# PowerStage.net
KiCad netlist of a schematic drawn in Altium Designer
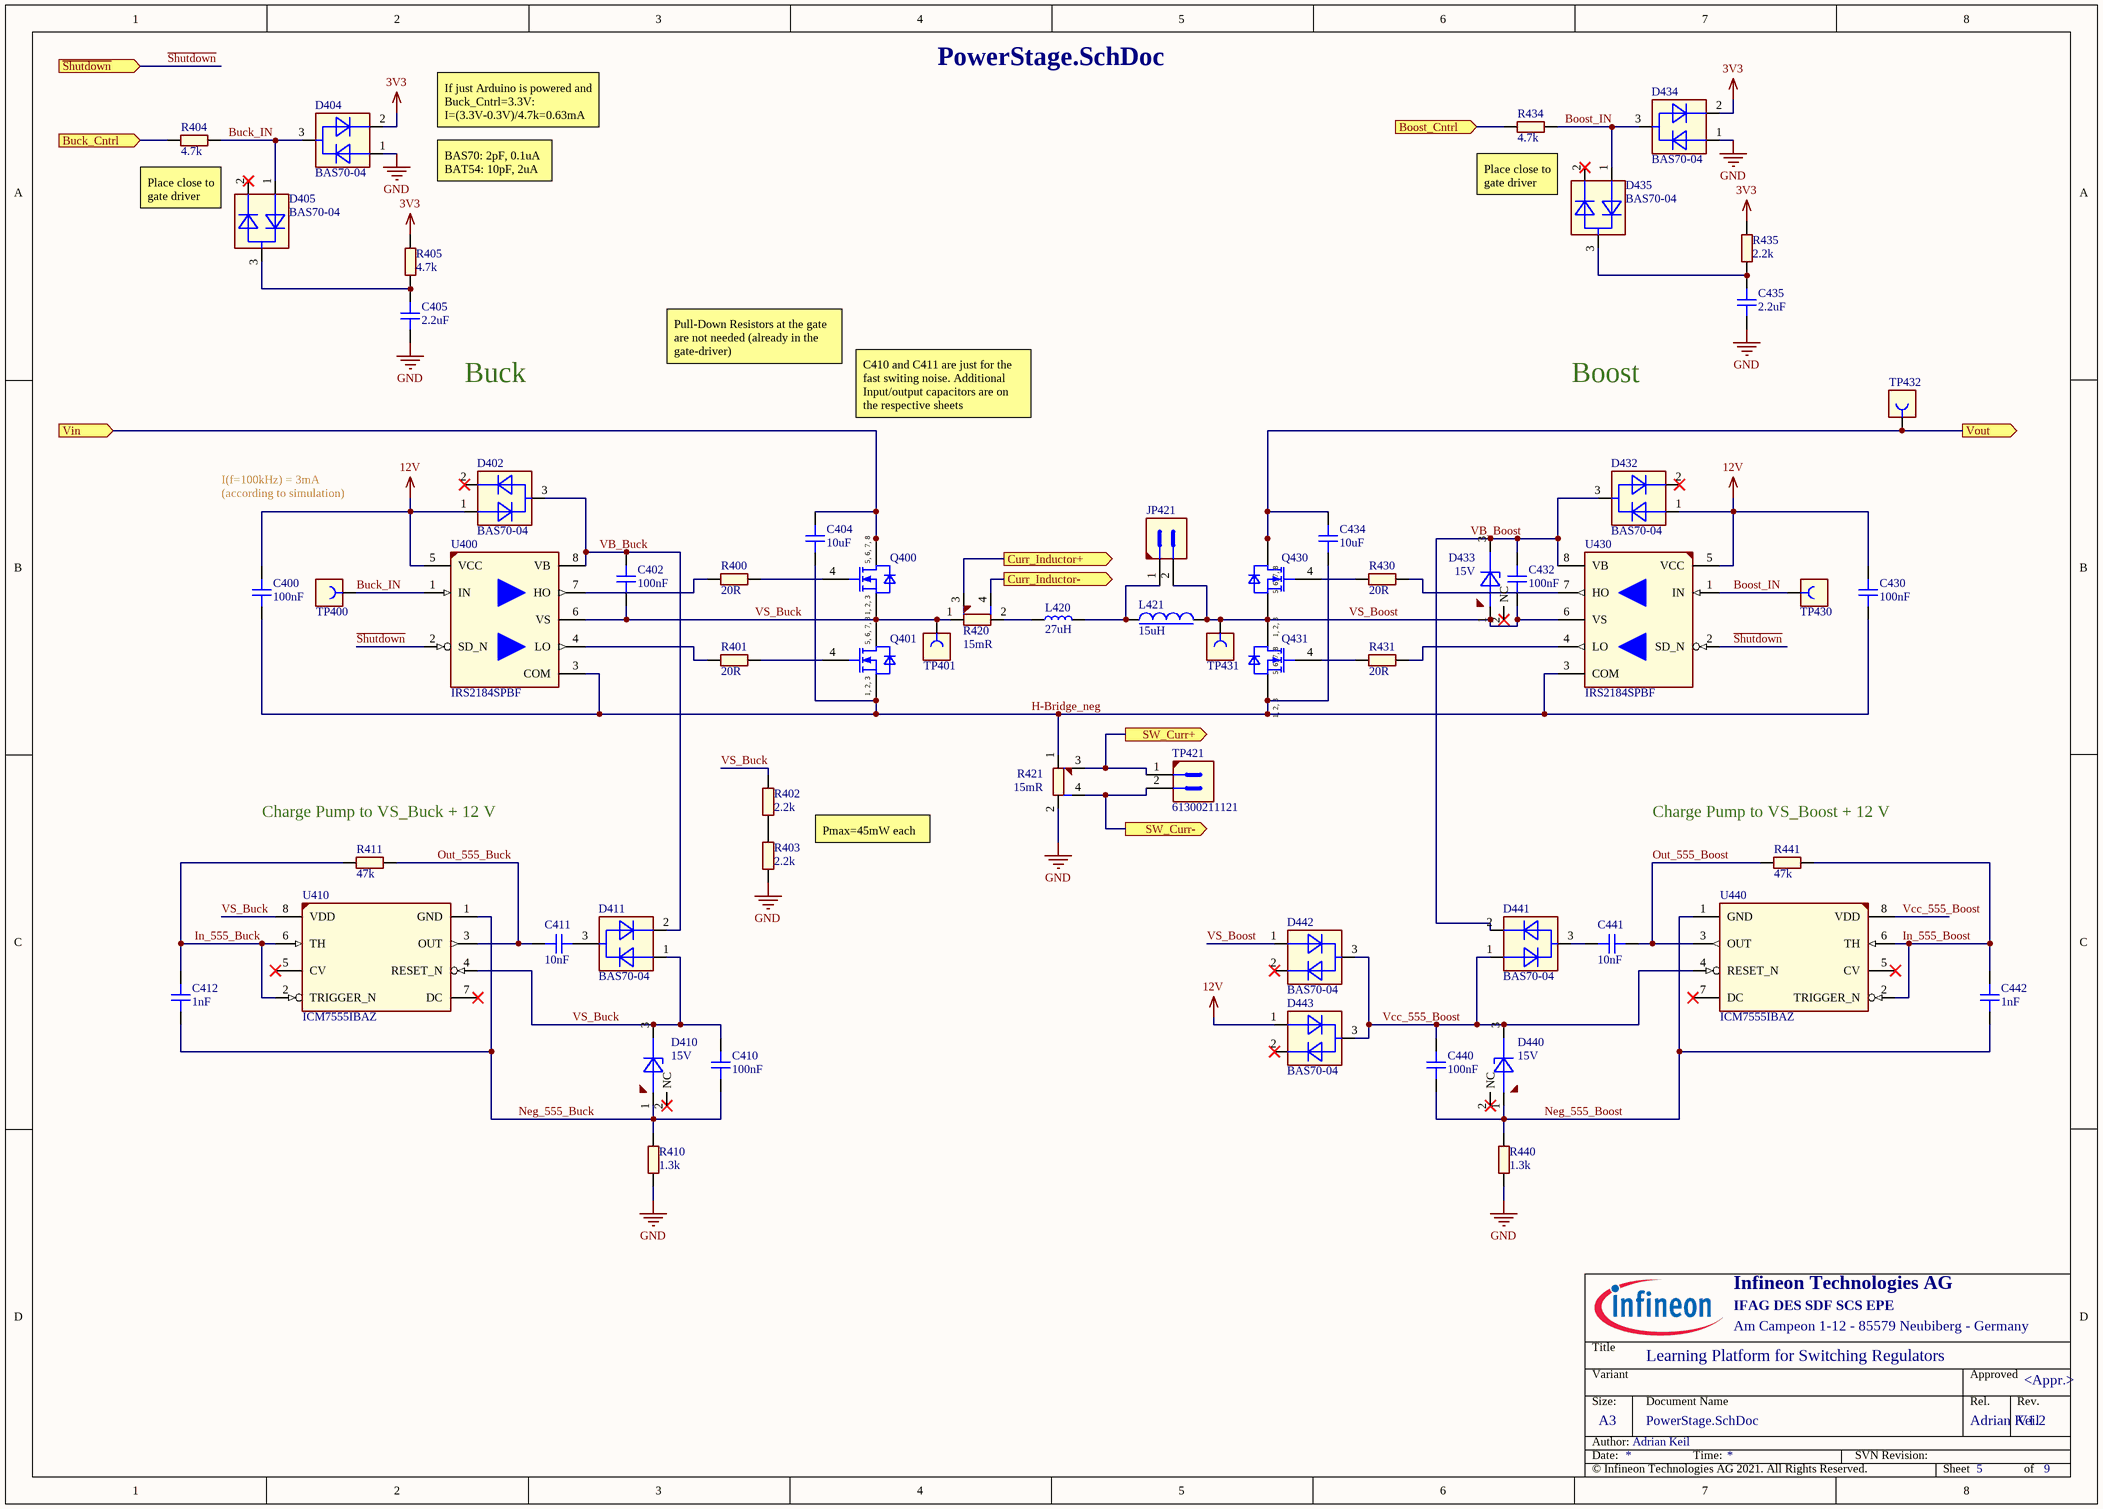
[diagram p0: PowerStage.SchDoc]

(export (version "E")
  (design (tool "Eeschema 10.0.6"))
  (components
    (comp (ref "C400")
      (value "100nF")
      (footprint "CAPC1608X90N-2")
      (description "CAP / CERA / 100nF / 50V / 10% / X7R (EIA) / -55°C to 125°C / 0603 / SMD / -")
      (fields (field (name "MANUFACTURER") "AVX"))
      (libsource (lib "PCBLibraryData") (part "CAP-SGL-STD-02P_00000001"))
    )
    (comp (ref "C402")
      (value "100nF")
      (footprint "CAPC1608X90N-2")
      (description "CAP / CERA / 100nF / 50V / 10% / X7R (EIA) / -55°C to 125°C / 0603 / SMD / -")
      (fields (field (name "MANUFACTURER") "AVX"))
      (libsource (lib "PCBLibraryData") (part "CAP-SGL-STD-02P_00000001"))
    )
    (comp (ref "C404")
      (value "10uF")
      (footprint "CAPC3216X190N-1")
      (description "CAP / CERA / 10uF / 50V / 20% / X5R (EIA) / -55°C to 85°C / 1206 (3216) / SMD / -")
      (fields (field (name "MANUFACTURER") "Taiyo Yuden"))
      (libsource (lib "PCBLibraryData") (part "CAP-SGL-STD-02P_00000001"))
    )
    (comp (ref "C405")
      (value "2.2uF")
      (footprint "CAPC1608X90N-3")
      (description "CAP / CERA / 2.2uF / 25V / 10% / X5R (EIA) / -55°C to 85°C / 0603(1608) / SMD / -")
      (fields (field (name "LEGACY PARTNUMBER") "CAP01010924") (field (name "MANUFACTURER") "MuRata"))
      (libsource (lib "PCBLibraryData") (part "CAP-SGL-STD-02P_00000001"))
    )
    (comp (ref "C410")
      (value "100nF")
      (footprint "CAPC1608X90N-2")
      (description "CAP / CERA / 100nF / 50V / 10% / X7R (EIA) / -55°C to 125°C / 0603 / SMD / -")
      (fields (field (name "MANUFACTURER") "AVX"))
      (libsource (lib "PCBLibraryData") (part "CAP-SGL-STD-02P_00000001"))
    )
    (comp (ref "C411")
      (value "10nF")
      (footprint "CAPC1608X90N-4")
      (description "CAP / CERA / 10nF / 50V / 10% / X8R (EIA) / -55°C to 150°C / 0603(1608) / SMD / -")
      (fields
        (field (name "LEGACY PARTNUMBER") "CAP01010834")
        (field (name "MANUFACTURER") "TDK Corporation")
      )
      (libsource (lib "PCBLibraryData") (part "CAP-SGL-STD-02P_00000001"))
    )
    (comp (ref "C412")
      (value "1nF")
      (footprint "CAPC1608X87N-1")
      (description "CAP / CERA / 1nF / 50V / 10% / X7R (EIA) / -55°C to 125°C / 0603 (1608) / SMD / -")
      (fields (field (name "MANUFACTURER") "Wurth Elektronik"))
      (libsource (lib "PCBLibraryData") (part "CAP-SGL-STD-02P_00000001"))
    )
    (comp (ref "C430")
      (value "100nF")
      (footprint "CAPC1608X90N-2")
      (description "CAP / CERA / 100nF / 50V / 10% / X7R (EIA) / -55°C to 125°C / 0603 / SMD / -")
      (fields (field (name "MANUFACTURER") "AVX"))
      (libsource (lib "PCBLibraryData") (part "CAP-SGL-STD-02P_00000001"))
    )
    (comp (ref "C432")
      (value "100nF")
      (footprint "CAPC1608X90N-2")
      (description "CAP / CERA / 100nF / 50V / 10% / X7R (EIA) / -55°C to 125°C / 0603 / SMD / -")
      (fields (field (name "MANUFACTURER") "AVX"))
      (libsource (lib "PCBLibraryData") (part "CAP-SGL-STD-02P_00000001"))
    )
    (comp (ref "C434")
      (value "10uF")
      (footprint "CAPC3216X190N-1")
      (description "CAP / CERA / 10uF / 50V / 20% / X5R (EIA) / -55°C to 85°C / 1206 (3216) / SMD / -")
      (fields (field (name "MANUFACTURER") "Taiyo Yuden"))
      (libsource (lib "PCBLibraryData") (part "CAP-SGL-STD-02P_00000001"))
    )
    (comp (ref "C435")
      (value "2.2uF")
      (footprint "CAPC1608X90N-3")
      (description "CAP / CERA / 2.2uF / 25V / 10% / X5R (EIA) / -55°C to 85°C / 0603(1608) / SMD / -")
      (fields (field (name "LEGACY PARTNUMBER") "CAP01010924") (field (name "MANUFACTURER") "MuRata"))
      (libsource (lib "PCBLibraryData") (part "CAP-SGL-STD-02P_00000001"))
    )
    (comp (ref "C440")
      (value "100nF")
      (footprint "CAPC1608X90N-2")
      (description "CAP / CERA / 100nF / 50V / 10% / X7R (EIA) / -55°C to 125°C / 0603 / SMD / -")
      (fields (field (name "MANUFACTURER") "AVX"))
      (libsource (lib "PCBLibraryData") (part "CAP-SGL-STD-02P_00000001"))
    )
    (comp (ref "C441")
      (value "10nF")
      (footprint "CAPC1608X90N-4")
      (description "CAP / CERA / 10nF / 50V / 10% / X8R (EIA) / -55°C to 150°C / 0603(1608) / SMD / -")
      (fields
        (field (name "LEGACY PARTNUMBER") "CAP01010834")
        (field (name "MANUFACTURER") "TDK Corporation")
      )
      (libsource (lib "PCBLibraryData") (part "CAP-SGL-STD-02P_00000001"))
    )
    (comp (ref "C442")
      (value "1nF")
      (footprint "CAPC1608X87N-1")
      (description "CAP / CERA / 1nF / 50V / 10% / X7R (EIA) / -55°C to 125°C / 0603 (1608) / SMD / -")
      (fields (field (name "MANUFACTURER") "Wurth Elektronik"))
      (libsource (lib "PCBLibraryData") (part "CAP-SGL-STD-02P_00000001"))
    )
    (comp (ref "D402")
      (value "BAS70-04")
      (footprint "SOT95P240X110-3N-1")
      (description "Silicon Schottky Diode")
      (fields
        (field (name "LEGACY PARTNUMBER") "IFX01400573")
        (field (name "MANUFACTURER") "Infineon Technologies")
      )
      (libsource (lib "") (part "d_dual_a1c2ac3_3p_1"))
    )
    (comp (ref "D404")
      (value "BAS70-04")
      (footprint "SOT95P240X110-3N-1")
      (description "Silicon Schottky Diode")
      (fields
        (field (name "LEGACY PARTNUMBER") "IFX01400573")
        (field (name "MANUFACTURER") "Infineon Technologies")
      )
      (libsource (lib "") (part "d_dual_a1c2ac3_3p_3"))
    )
    (comp (ref "D405")
      (value "BAS70-04")
      (footprint "SOT95P240X110-3N-1")
      (description "Silicon Schottky Diode")
      (fields
        (field (name "LEGACY PARTNUMBER") "IFX01400573")
        (field (name "MANUFACTURER") "Infineon Technologies")
      )
      (libsource (lib "PCBLibraryData") (part "d_dual_a1c2ac3_3p"))
    )
    (comp (ref "D410")
      (value "15V")
      (footprint "SOT95P230X110-3N")
      (description "Voltage regulator diodes")
      (fields (field (name "MANUFACTURER") "Nexperia"))
      (libsource (lib "PCBLibraryData") (part "d_zener_a1c3_3p"))
    )
    (comp (ref "D411")
      (value "BAS70-04")
      (footprint "SOT95P240X110-3N-1")
      (description "Silicon Schottky Diode")
      (fields
        (field (name "LEGACY PARTNUMBER") "IFX01400573")
        (field (name "MANUFACTURER") "Infineon Technologies")
      )
      (libsource (lib "") (part "d_dual_a1c2ac3_3p_3"))
    )
    (comp (ref "D432")
      (value "BAS70-04")
      (footprint "SOT95P240X110-3N-1")
      (description "Silicon Schottky Diode")
      (fields
        (field (name "LEGACY PARTNUMBER") "IFX01400573")
        (field (name "MANUFACTURER") "Infineon Technologies")
      )
      (libsource (lib "") (part "d_dual_a1c2ac3_3p_3"))
    )
    (comp (ref "D433")
      (value "15V")
      (footprint "SOT95P230X110-3N")
      (description "Voltage regulator diodes")
      (fields (field (name "MANUFACTURER") "Nexperia"))
      (libsource (lib "PCBLibraryData") (part "d_zener_a1c3_3p"))
    )
    (comp (ref "D434")
      (value "BAS70-04")
      (footprint "SOT95P240X110-3N-1")
      (description "Silicon Schottky Diode")
      (fields
        (field (name "LEGACY PARTNUMBER") "IFX01400573")
        (field (name "MANUFACTURER") "Infineon Technologies")
      )
      (libsource (lib "") (part "d_dual_a1c2ac3_3p_3"))
    )
    (comp (ref "D435")
      (value "BAS70-04")
      (footprint "SOT95P240X110-3N-1")
      (description "Silicon Schottky Diode")
      (fields
        (field (name "LEGACY PARTNUMBER") "IFX01400573")
        (field (name "MANUFACTURER") "Infineon Technologies")
      )
      (libsource (lib "PCBLibraryData") (part "d_dual_a1c2ac3_3p"))
    )
    (comp (ref "D440")
      (value "15V")
      (footprint "SOT95P230X110-3N")
      (description "Voltage regulator diodes")
      (fields (field (name "MANUFACTURER") "Nexperia"))
      (libsource (lib "PCBLibraryData") (part "d_zener_a1c3_3p"))
    )
    (comp (ref "D441")
      (value "BAS70-04")
      (footprint "SOT95P240X110-3N-1")
      (description "Silicon Schottky Diode")
      (fields
        (field (name "LEGACY PARTNUMBER") "IFX01400573")
        (field (name "MANUFACTURER") "Infineon Technologies")
      )
      (libsource (lib "") (part "d_dual_a1c2ac3_3p_1"))
    )
    (comp (ref "D442")
      (value "BAS70-04")
      (footprint "SOT95P240X110-3N-1")
      (description "Silicon Schottky Diode")
      (fields
        (field (name "LEGACY PARTNUMBER") "IFX01400573")
        (field (name "MANUFACTURER") "Infineon Technologies")
      )
      (libsource (lib "") (part "d_dual_a1c2ac3_3p_2"))
    )
    (comp (ref "D443")
      (value "BAS70-04")
      (footprint "SOT95P240X110-3N-1")
      (description "Silicon Schottky Diode")
      (fields
        (field (name "LEGACY PARTNUMBER") "IFX01400573")
        (field (name "MANUFACTURER") "Infineon Technologies")
      )
      (libsource (lib "") (part "d_dual_a1c2ac3_3p_2"))
    )
    (comp (ref "JP421")
      (value "61300211121")
      (footprint "CON-M-THT-61300211121")
      (description "Header, 2.54mm Pitch, 2 pin, Vertical, Single Row")
      (fields
        (field (name "LEGACY PARTNUMBER") "CON01500943")
        (field (name "MANUFACTURER") "Wurth Elektronik")
      )
      (libsource (lib "") (part "Header 2_1"))
    )
    (comp (ref "L420")
      (value "27uH")
      (footprint "INDM120120X1000N")
      (fields (field (name "MANUFACTURER") "Wurth Elektronik"))
      (libsource (lib "PCBLibraryData") (part "IND-SGL-STD-02P_00000015"))
    )
    (comp (ref "L421")
      (value "15uH")
      (footprint "IND-SMD-SRP6060FA")
      (fields (field (name "MANUFACTURER") "Bourns"))
      (libsource (lib "PCBLibraryData") (part "IND-SGL-STD-COR-02P_00000016"))
    )
    (comp (ref "Q400")
      (value "igfet_n_ch_enh_dio_1s2s3s4g5d6d7d8d_8p")
      (footprint "INF-PG-TSDSON-8-FL")
      (description "OptiMOS Power - MOSFET, 60 V")
      (fields
        (field (name "LEGACY PARTNUMBER") "IFX01400359")
        (field (name "MANUFACTURER") "Infineon Technologies")
      )
      (libsource (lib "PCBLibraryData") (part "igfet_n_ch_enh_dio_1s2s3s4g5d6d7d8d_8p"))
    )
    (comp (ref "Q401")
      (value "igfet_n_ch_enh_dio_1s2s3s4g5d6d7d8d_8p")
      (footprint "INF-PG-TSDSON-8-FL")
      (description "OptiMOS Power - MOSFET, 60 V")
      (fields
        (field (name "LEGACY PARTNUMBER") "IFX01400359")
        (field (name "MANUFACTURER") "Infineon Technologies")
      )
      (libsource (lib "PCBLibraryData") (part "igfet_n_ch_enh_dio_1s2s3s4g5d6d7d8d_8p"))
    )
    (comp (ref "Q430")
      (value "igfet_n_ch_enh_dio_1s2s3s4g5d6d7d8d_8p")
      (footprint "INF-PG-TSDSON-8-FL")
      (description "OptiMOS Power - MOSFET, 60 V")
      (fields
        (field (name "LEGACY PARTNUMBER") "IFX01400359")
        (field (name "MANUFACTURER") "Infineon Technologies")
      )
      (libsource (lib "PCBLibraryData") (part "igfet_n_ch_enh_dio_1s2s3s4g5d6d7d8d_8p"))
    )
    (comp (ref "Q431")
      (value "igfet_n_ch_enh_dio_1s2s3s4g5d6d7d8d_8p")
      (footprint "INF-PG-TSDSON-8-FL")
      (description "OptiMOS Power - MOSFET, 60 V")
      (fields
        (field (name "LEGACY PARTNUMBER") "IFX01400359")
        (field (name "MANUFACTURER") "Infineon Technologies")
      )
      (libsource (lib "PCBLibraryData") (part "igfet_n_ch_enh_dio_1s2s3s4g5d6d7d8d_8p"))
    )
    (comp (ref "R400")
      (value "20R")
      (footprint "RESC1609X50N")
      (description "RES / STD / 20R / 100mW / 1% / 100ppm/K / -55°C to 155°C / 0603 / SMD / -")
      (fields (field (name "LEGACY PARTNUMBER") "RES01800947") (field (name "MANUFACTURER") "Vishay"))
      (libsource (lib "PCBLibraryData") (part "RES-SGL-STD-02P_00000006"))
    )
    (comp (ref "R401")
      (value "20R")
      (footprint "RESC1609X50N")
      (description "RES / STD / 20R / 100mW / 1% / 100ppm/K / -55°C to 155°C / 0603 / SMD / -")
      (fields (field (name "LEGACY PARTNUMBER") "RES01800947") (field (name "MANUFACTURER") "Vishay"))
      (libsource (lib "PCBLibraryData") (part "RES-SGL-STD-02P_00000006"))
    )
    (comp (ref "R402")
      (value "2.2k")
      (footprint "RESC1609X50N")
      (description "RES / STD / 2.2k / 100mW / 1% / 100ppm/K / -55°C to 155°C / 0603 / SMD / -")
      (fields (field (name "LEGACY PARTNUMBER") "RES01801179") (field (name "MANUFACTURER") "Vishay"))
      (libsource (lib "") (part "RES-SGL-STD-02P_00000006_1"))
    )
    (comp (ref "R403")
      (value "2.2k")
      (footprint "RESC1609X50N")
      (description "RES / STD / 2.2k / 100mW / 1% / 100ppm/K / -55°C to 155°C / 0603 / SMD / -")
      (fields (field (name "LEGACY PARTNUMBER") "RES01801179") (field (name "MANUFACTURER") "Vishay"))
      (libsource (lib "") (part "RES-SGL-STD-02P_00000006_1"))
    )
    (comp (ref "R404")
      (value "4.7k")
      (footprint "RESC1609X50N")
      (description "RES / STD / 4.7k / 100mW / 1% / 100ppm/K / -55°C to 155°C / 0603 / SMD / -")
      (fields (field (name "LEGACY PARTNUMBER") "RES01801219") (field (name "MANUFACTURER") "Vishay"))
      (libsource (lib "") (part "RES-SGL-STD-02P_00000006_3"))
    )
    (comp (ref "R405")
      (value "4.7k")
      (footprint "RESC1609X50N")
      (description "RES / STD / 4.7k / 100mW / 1% / 100ppm/K / -55°C to 155°C / 0603 / SMD / -")
      (fields (field (name "LEGACY PARTNUMBER") "RES01801219") (field (name "MANUFACTURER") "Vishay"))
      (libsource (lib "") (part "RES-SGL-STD-02P_00000006_2"))
    )
    (comp (ref "R410")
      (value "1.3k")
      (footprint "RESC1609X50N")
      (description "RES / STD / 1.3k / 100mW / 1% / 100ppm/K / -55°C to 155°C / 0603 / SMD / -")
      (fields (field (name "LEGACY PARTNUMBER") "RES01801155") (field (name "MANUFACTURER") "Vishay"))
      (libsource (lib "") (part "RES-SGL-STD-02P_00000006_2"))
    )
    (comp (ref "R411")
      (value "47k")
      (footprint "RESC1609X50N")
      (description "RES / STD / 47k / 100mW / 1% / 100ppm/K / -55°C to 155°C / 0603 / SMD / -")
      (fields (field (name "LEGACY PARTNUMBER") "RES01801333") (field (name "MANUFACTURER") "Vishay"))
      (libsource (lib "PCBLibraryData") (part "RES-SGL-STD-02P_00000006"))
    )
    (comp (ref "R420")
      (value "15mR")
      (footprint "RES-SMD-L4T12")
      (description "RES / STD / 15mR / 500mW / 1% / 75ppm/K / -55°C to 155°C / 1206 (3216) / SMD / -")
      (fields (field (name "MANUFACTURER") "Ohmite"))
      (libsource (lib "") (part "RES-SHT-STD-04P_00097BE5_1"))
    )
    (comp (ref "R421")
      (value "15mR")
      (footprint "RES-SMD-L4T12")
      (description "RES / STD / 15mR / 500mW / 1% / 75ppm/K / -55°C to 155°C / 1206 (3216) / SMD / -")
      (fields (field (name "MANUFACTURER") "Ohmite"))
      (libsource (lib "PCBLibraryData") (part "RES-SHT-STD-04P_00097BE5"))
    )
    (comp (ref "R430")
      (value "20R")
      (footprint "RESC1609X50N")
      (description "RES / STD / 20R / 100mW / 1% / 100ppm/K / -55°C to 155°C / 0603 / SMD / -")
      (fields (field (name "LEGACY PARTNUMBER") "RES01800947") (field (name "MANUFACTURER") "Vishay"))
      (libsource (lib "PCBLibraryData") (part "RES-SGL-STD-02P_00000006"))
    )
    (comp (ref "R431")
      (value "20R")
      (footprint "RESC1609X50N")
      (description "RES / STD / 20R / 100mW / 1% / 100ppm/K / -55°C to 155°C / 0603 / SMD / -")
      (fields (field (name "LEGACY PARTNUMBER") "RES01800947") (field (name "MANUFACTURER") "Vishay"))
      (libsource (lib "PCBLibraryData") (part "RES-SGL-STD-02P_00000006"))
    )
    (comp (ref "R434")
      (value "4.7k")
      (footprint "RESC1609X50N")
      (description "RES / STD / 4.7k / 100mW / 1% / 100ppm/K / -55°C to 155°C / 0603 / SMD / -")
      (fields (field (name "LEGACY PARTNUMBER") "RES01801219") (field (name "MANUFACTURER") "Vishay"))
      (libsource (lib "") (part "RES-SGL-STD-02P_00000006_3"))
    )
    (comp (ref "R435")
      (value "2.2k")
      (footprint "RESC1609X50N")
      (description "RES / STD / 2.2k / 100mW / 1% / 100ppm/K / -55°C to 155°C / 0603 / SMD / -")
      (fields (field (name "LEGACY PARTNUMBER") "RES01801179") (field (name "MANUFACTURER") "Vishay"))
      (libsource (lib "") (part "RES-SGL-STD-02P_00000006_1"))
    )
    (comp (ref "R440")
      (value "1.3k")
      (footprint "RESC1609X50N")
      (description "RES / STD / 1.3k / 100mW / 1% / 100ppm/K / -55°C to 155°C / 0603 / SMD / -")
      (fields (field (name "LEGACY PARTNUMBER") "RES01801155") (field (name "MANUFACTURER") "Vishay"))
      (libsource (lib "") (part "RES-SGL-STD-02P_00000006_2"))
    )
    (comp (ref "R441")
      (value "47k")
      (footprint "RESC1609X50N")
      (description "RES / STD / 47k / 100mW / 1% / 100ppm/K / -55°C to 155°C / 0603 / SMD / -")
      (fields (field (name "LEGACY PARTNUMBER") "RES01801333") (field (name "MANUFACTURER") "Vishay"))
      (libsource (lib "") (part "RES-SGL-STD-02P_00000006_2"))
    )
    (comp (ref "TP400")
      (value "S1751-46R")
      (footprint "CON-SMD-TT-S1751-46")
      (description "Test Terminal, Surface Mount (Tape and Reeled Components)")
      (fields (field (name "LEGACY PARTNUMBER") "CON01501015") (field (name "MANUFACTURER") "Harwin"))
      (libsource (lib "") (part "connector_1_f_2"))
    )
    (comp (ref "TP401")
      (value "S1751-46R")
      (footprint "CON-SMD-TT-S1751-46")
      (description "Test Terminal, Surface Mount (Tape and Reeled Components)")
      (fields (field (name "LEGACY PARTNUMBER") "CON01501015") (field (name "MANUFACTURER") "Harwin"))
      (libsource (lib "PCBLibraryData") (part "connector_1_f"))
    )
    (comp (ref "TP421")
      (value "61300211121")
      (footprint "CON-M-THT-61300211121")
      (description "Header, 2.54mm Pitch, 2 pin, Vertical, Single Row")
      (fields
        (field (name "LEGACY PARTNUMBER") "CON01500943")
        (field (name "MANUFACTURER") "Wurth Elektronik")
      )
      (libsource (lib "PCBLibraryData") (part "Header 2"))
    )
    (comp (ref "TP430")
      (value "S1751-46R")
      (footprint "CON-SMD-TT-S1751-46")
      (description "Test Terminal, Surface Mount (Tape and Reeled Components)")
      (fields (field (name "LEGACY PARTNUMBER") "CON01501015") (field (name "MANUFACTURER") "Harwin"))
      (libsource (lib "") (part "connector_1_f_3"))
    )
    (comp (ref "TP431")
      (value "S1751-46R")
      (footprint "CON-SMD-TT-S1751-46")
      (description "Test Terminal, Surface Mount (Tape and Reeled Components)")
      (fields (field (name "LEGACY PARTNUMBER") "CON01501015") (field (name "MANUFACTURER") "Harwin"))
      (libsource (lib "PCBLibraryData") (part "connector_1_f"))
    )
    (comp (ref "TP432")
      (value "S1751-46R")
      (footprint "CON-SMD-TT-S1751-46")
      (description "Test Terminal, Surface Mount (Tape and Reeled Components)")
      (fields (field (name "LEGACY PARTNUMBER") "CON01501015") (field (name "MANUFACTURER") "Harwin"))
      (libsource (lib "") (part "connector_1_f_1"))
    )
    (comp (ref "U400")
      (value "IRS2184SPBF")
      (footprint "SOIC127P600X175-8N-12-V")
      (fields (field (name "MANUFACTURER") "Infineon Technologies"))
      (libsource (lib "PCBLibraryData") (part "IRS2184S"))
    )
    (comp (ref "U410")
      (value "ICM7555IBAZ")
      (footprint "SOIC127P600X175-8N-12")
      (description "General Purpose Timers")
      (fields (field (name "MANUFACTURER") "Renesas"))
      (libsource (lib "") (part "ICM7555_1"))
    )
    (comp (ref "U430")
      (value "IRS2184SPBF")
      (footprint "SOIC127P600X175-8N-12-V")
      (fields (field (name "MANUFACTURER") "Infineon Technologies"))
      (libsource (lib "") (part "IRS2184S_1"))
    )
    (comp (ref "U440")
      (value "ICM7555IBAZ")
      (footprint "SOIC127P600X175-8N-12")
      (description "General Purpose Timers")
      (fields (field (name "MANUFACTURER") "Renesas"))
      (libsource (lib "PCBLibraryData") (part "ICM7555"))
    )
  )
  (nets
    (net (code "1") (name "/Boost_Cntrl") (class "Default")
      (node (ref "R434") (pin "1") (pinfunction "1_1") (pintype "passive"))
    )
    (net (code "2") (name "/Boost_IN") (class "Default")
      (node (ref "D434") (pin "3") (pinfunction "ANODE_/_CATHODE_3") (pintype "passive"))
      (node (ref "D435") (pin "1") (pinfunction "ANODE_1") (pintype "passive"))
      (node (ref "R434") (pin "2") (pinfunction "2_2") (pintype "passive"))
      (node (ref "TP430") (pin "1") (pinfunction "1_1") (pintype "passive"))
      (node (ref "U430") (pin "1") (pinfunction "IN_1") (pintype "input"))
    )
    (net (code "3") (name "/Buck_Cntrl") (class "Default")
      (node (ref "R404") (pin "1") (pinfunction "1_1") (pintype "passive"))
    )
    (net (code "4") (name "/Buck_IN") (class "Default")
      (node (ref "D404") (pin "3") (pinfunction "ANODE_/_CATHODE_3") (pintype "passive"))
      (node (ref "D405") (pin "1") (pinfunction "ANODE_1") (pintype "passive"))
      (node (ref "R404") (pin "2") (pinfunction "2_2") (pintype "passive"))
      (node (ref "TP400") (pin "1") (pinfunction "1_1") (pintype "passive"))
      (node (ref "U400") (pin "1") (pinfunction "IN_1") (pintype "input"))
    )
    (net (code "5") (name "/Curr_Inductor+") (class "Default")
      (node (ref "R420") (pin "3") (pinfunction "I1_3") (pintype "passive"))
    )
    (net (code "6") (name "/Curr_Inductor-") (class "Default")
      (node (ref "R420") (pin "4") (pinfunction "I2_4") (pintype "passive"))
    )
    (net (code "7") (name "/H-Bridge_neg") (class "Default")
      (node (ref "C400") (pin "1") (pinfunction "1_1") (pintype "passive"))
      (node (ref "C404") (pin "1") (pinfunction "1_1") (pintype "passive"))
      (node (ref "C430") (pin "1") (pinfunction "1_1") (pintype "passive"))
      (node (ref "C434") (pin "1") (pinfunction "1_1") (pintype "passive"))
      (node (ref "Q401") (pin "1") (pinfunction "SOURCE_1") (pintype "passive"))
      (node (ref "Q401") (pin "2") (pinfunction "SOURCE_2") (pintype "passive"))
      (node (ref "Q401") (pin "3") (pinfunction "SOURCE_3") (pintype "passive"))
      (node (ref "Q431") (pin "1") (pinfunction "SOURCE_1") (pintype "passive"))
      (node (ref "Q431") (pin "2") (pinfunction "SOURCE_2") (pintype "passive"))
      (node (ref "Q431") (pin "3") (pinfunction "SOURCE_3") (pintype "passive"))
      (node (ref "R421") (pin "1") (pinfunction "V1_1") (pintype "passive"))
      (node (ref "U400") (pin "3") (pinfunction "COM_3") (pintype "passive"))
      (node (ref "U430") (pin "3") (pinfunction "COM_3") (pintype "passive"))
    )
    (net (code "8") (name "/In_555_Boost") (class "Default")
      (node (ref "C442") (pin "2") (pinfunction "2_2") (pintype "passive"))
      (node (ref "R441") (pin "2") (pinfunction "2_2") (pintype "passive"))
      (node (ref "U440") (pin "2") (pinfunction "TRIGGER_N_2") (pintype "input"))
      (node (ref "U440") (pin "6") (pinfunction "TH_6") (pintype "input"))
    )
    (net (code "9") (name "/In_555_Buck") (class "Default")
      (node (ref "C412") (pin "2") (pinfunction "2_2") (pintype "passive"))
      (node (ref "R411") (pin "2") (pinfunction "2_2") (pintype "passive"))
      (node (ref "U410") (pin "2") (pinfunction "TRIGGER_N_2") (pintype "input"))
      (node (ref "U410") (pin "6") (pinfunction "TH_6") (pintype "input"))
    )
    (net (code "10") (name "/Neg_555_Boost") (class "Default")
      (node (ref "C440") (pin "1") (pinfunction "1_1") (pintype "passive"))
      (node (ref "C442") (pin "1") (pinfunction "1_1") (pintype "passive"))
      (node (ref "D440") (pin "1") (pinfunction "ANODE_1") (pintype "passive"))
      (node (ref "R440") (pin "2") (pinfunction "2_2") (pintype "passive"))
      (node (ref "U440") (pin "1") (pinfunction "GND_1") (pintype "power_in"))
    )
    (net (code "11") (name "/Neg_555_Buck") (class "Default")
      (node (ref "C410") (pin "1") (pinfunction "1_1") (pintype "passive"))
      (node (ref "C412") (pin "1") (pinfunction "1_1") (pintype "passive"))
      (node (ref "D410") (pin "1") (pinfunction "ANODE_1") (pintype "passive"))
      (node (ref "R410") (pin "2") (pinfunction "2_2") (pintype "passive"))
      (node (ref "U410") (pin "1") (pinfunction "GND_1") (pintype "power_in"))
    )
    (net (code "12") (name "/Out_555_Boost") (class "Default")
      (node (ref "C441") (pin "1") (pinfunction "1_1") (pintype "passive"))
      (node (ref "R441") (pin "1") (pinfunction "1_1") (pintype "passive"))
      (node (ref "U440") (pin "3") (pinfunction "OUT_3") (pintype "output"))
    )
    (net (code "13") (name "/Out_555_Buck") (class "Default")
      (node (ref "C411") (pin "2") (pinfunction "2_2") (pintype "passive"))
      (node (ref "R411") (pin "1") (pinfunction "1_1") (pintype "passive"))
      (node (ref "U410") (pin "3") (pinfunction "OUT_3") (pintype "output"))
    )
    (net (code "14") (name "/SW_Curr+") (class "Default")
      (node (ref "R421") (pin "3") (pinfunction "I1_3") (pintype "passive"))
      (node (ref "TP421") (pin "1") (pinfunction "1_1") (pintype "passive"))
    )
    (net (code "15") (name "/SW_Curr-") (class "Default")
      (node (ref "R421") (pin "4") (pinfunction "I2_4") (pintype "passive"))
      (node (ref "TP421") (pin "2") (pinfunction "2_2") (pintype "passive"))
    )
    (net (code "16") (name "/Shutdown") (class "Default")
      (node (ref "U400") (pin "2") (pinfunction "SD_N_2") (pintype "input"))
      (node (ref "U430") (pin "2") (pinfunction "SD_N_2") (pintype "input"))
    )
    (net (code "17") (name "/VB_Boost") (class "Default")
      (node (ref "C432") (pin "2") (pinfunction "2_2") (pintype "passive"))
      (node (ref "D432") (pin "3") (pinfunction "ANODE_/_CATHODE_3") (pintype "passive"))
      (node (ref "D433") (pin "3") (pinfunction "CATHODE_3") (pintype "passive"))
      (node (ref "D441") (pin "2") (pinfunction "CATHODE_2") (pintype "passive"))
      (node (ref "U430") (pin "8") (pinfunction "VB_8") (pintype "power_in"))
    )
    (net (code "18") (name "/VB_Buck") (class "Default")
      (node (ref "C402") (pin "2") (pinfunction "2_2") (pintype "passive"))
      (node (ref "D402") (pin "3") (pinfunction "ANODE_/_CATHODE_3") (pintype "passive"))
      (node (ref "D411") (pin "2") (pinfunction "CATHODE_2") (pintype "passive"))
      (node (ref "U400") (pin "8") (pinfunction "VB_8") (pintype "power_in"))
    )
    (net (code "19") (name "/VS_Boost") (class "Default")
      (node (ref "C432") (pin "1") (pinfunction "1_1") (pintype "passive"))
      (node (ref "D433") (pin "1") (pinfunction "ANODE_1") (pintype "passive"))
      (node (ref "D442") (pin "1") (pinfunction "ANODE_1") (pintype "passive"))
      (node (ref "JP421") (pin "2") (pinfunction "2_2") (pintype "passive"))
      (node (ref "L421") (pin "2") (pinfunction "2_2") (pintype "passive"))
      (node (ref "Q430") (pin "1") (pinfunction "SOURCE_1") (pintype "passive"))
      (node (ref "Q430") (pin "2") (pinfunction "SOURCE_2") (pintype "passive"))
      (node (ref "Q430") (pin "3") (pinfunction "SOURCE_3") (pintype "passive"))
      (node (ref "Q431") (pin "5") (pinfunction "DRAIN_5") (pintype "passive"))
      (node (ref "Q431") (pin "6") (pinfunction "DRAIN_6") (pintype "passive"))
      (node (ref "Q431") (pin "7") (pinfunction "DRAIN_7") (pintype "passive"))
      (node (ref "Q431") (pin "8") (pinfunction "DRAIN_8") (pintype "passive"))
      (node (ref "TP431") (pin "1") (pinfunction "1_1") (pintype "passive"))
      (node (ref "U430") (pin "6") (pinfunction "VS_6") (pintype "power_in"))
    )
    (net (code "20") (name "/VS_Buck") (class "Default")
      (node (ref "C402") (pin "1") (pinfunction "1_1") (pintype "passive"))
      (node (ref "C410") (pin "2") (pinfunction "2_2") (pintype "passive"))
      (node (ref "D410") (pin "3") (pinfunction "CATHODE_3") (pintype "passive"))
      (node (ref "D411") (pin "1") (pinfunction "ANODE_1") (pintype "passive"))
      (node (ref "Q400") (pin "1") (pinfunction "SOURCE_1") (pintype "passive"))
      (node (ref "Q400") (pin "2") (pinfunction "SOURCE_2") (pintype "passive"))
      (node (ref "Q400") (pin "3") (pinfunction "SOURCE_3") (pintype "passive"))
      (node (ref "Q401") (pin "5") (pinfunction "DRAIN_5") (pintype "passive"))
      (node (ref "Q401") (pin "6") (pinfunction "DRAIN_6") (pintype "passive"))
      (node (ref "Q401") (pin "7") (pinfunction "DRAIN_7") (pintype "passive"))
      (node (ref "Q401") (pin "8") (pinfunction "DRAIN_8") (pintype "passive"))
      (node (ref "R402") (pin "1") (pinfunction "1_1") (pintype "passive"))
      (node (ref "R420") (pin "1") (pinfunction "V1_1") (pintype "passive"))
      (node (ref "TP401") (pin "1") (pinfunction "1_1") (pintype "passive"))
      (node (ref "U400") (pin "6") (pinfunction "VS_6") (pintype "power_in"))
      (node (ref "U410") (pin "4") (pinfunction "RESET_N_4") (pintype "input"))
      (node (ref "U410") (pin "8") (pinfunction "VDD_8") (pintype "power_in"))
    )
    (net (code "21") (name "/Vcc_555_Boost") (class "Default")
      (node (ref "C440") (pin "2") (pinfunction "2_2") (pintype "passive"))
      (node (ref "D440") (pin "3") (pinfunction "CATHODE_3") (pintype "passive"))
      (node (ref "D441") (pin "1") (pinfunction "ANODE_1") (pintype "passive"))
      (node (ref "D442") (pin "3") (pinfunction "ANODE_/_CATHODE_3") (pintype "passive"))
      (node (ref "D443") (pin "3") (pinfunction "ANODE_/_CATHODE_3") (pintype "passive"))
      (node (ref "U440") (pin "4") (pinfunction "RESET_N_4") (pintype "input"))
      (node (ref "U440") (pin "8") (pinfunction "VDD_8") (pintype "power_in"))
    )
    (net (code "22") (name "/Vin") (class "Default")
      (node (ref "C404") (pin "2") (pinfunction "2_2") (pintype "passive"))
      (node (ref "Q400") (pin "5") (pinfunction "DRAIN_5") (pintype "passive"))
      (node (ref "Q400") (pin "6") (pinfunction "DRAIN_6") (pintype "passive"))
      (node (ref "Q400") (pin "7") (pinfunction "DRAIN_7") (pintype "passive"))
      (node (ref "Q400") (pin "8") (pinfunction "DRAIN_8") (pintype "passive"))
    )
    (net (code "23") (name "/Vout") (class "Default")
      (node (ref "C434") (pin "2") (pinfunction "2_2") (pintype "passive"))
      (node (ref "Q430") (pin "5") (pinfunction "DRAIN_5") (pintype "passive"))
      (node (ref "Q430") (pin "6") (pinfunction "DRAIN_6") (pintype "passive"))
      (node (ref "Q430") (pin "7") (pinfunction "DRAIN_7") (pintype "passive"))
      (node (ref "Q430") (pin "8") (pinfunction "DRAIN_8") (pintype "passive"))
      (node (ref "TP432") (pin "1") (pinfunction "1_1") (pintype "passive"))
    )
    (net (code "24") (name "3V3") (class "Default")
      (node (ref "D404") (pin "2") (pinfunction "CATHODE_2") (pintype "passive"))
      (node (ref "D434") (pin "2") (pinfunction "CATHODE_2") (pintype "passive"))
      (node (ref "R405") (pin "2") (pinfunction "2_2") (pintype "passive"))
      (node (ref "R435") (pin "1") (pinfunction "1_1") (pintype "passive"))
    )
    (net (code "25") (name "12V") (class "Default")
      (node (ref "C400") (pin "2") (pinfunction "2_2") (pintype "passive"))
      (node (ref "C430") (pin "2") (pinfunction "2_2") (pintype "passive"))
      (node (ref "D402") (pin "1") (pinfunction "ANODE_1") (pintype "passive"))
      (node (ref "D432") (pin "1") (pinfunction "ANODE_1") (pintype "passive"))
      (node (ref "D443") (pin "1") (pinfunction "ANODE_1") (pintype "passive"))
      (node (ref "U400") (pin "5") (pinfunction "VCC_5") (pintype "power_in"))
      (node (ref "U430") (pin "5") (pinfunction "VCC_5") (pintype "power_in"))
    )
    (net (code "26") (name "GND") (class "Default")
      (node (ref "C405") (pin "1") (pinfunction "1_1") (pintype "passive"))
      (node (ref "C435") (pin "1") (pinfunction "1_1") (pintype "passive"))
      (node (ref "D404") (pin "1") (pinfunction "ANODE_1") (pintype "passive"))
      (node (ref "D434") (pin "1") (pinfunction "ANODE_1") (pintype "passive"))
      (node (ref "R403") (pin "2") (pinfunction "2_2") (pintype "passive"))
      (node (ref "R410") (pin "1") (pinfunction "1_1") (pintype "passive"))
      (node (ref "R421") (pin "2") (pinfunction "V2_2") (pintype "passive"))
      (node (ref "R440") (pin "1") (pinfunction "1_1") (pintype "passive"))
    )
    (net (code "27") (name "Net-(D405-ANODE_{slash}_CATHODE)") (class "Default")
      (node (ref "C405") (pin "2") (pinfunction "2_2") (pintype "passive"))
      (node (ref "D405") (pin "3") (pinfunction "ANODE_/_CATHODE_3") (pintype "passive"))
      (node (ref "R405") (pin "1") (pinfunction "1_1") (pintype "passive"))
    )
    (net (code "28") (name "Net-(D411-ANODE_{slash}_CATHODE)") (class "Default")
      (node (ref "C411") (pin "1") (pinfunction "1_1") (pintype "passive"))
      (node (ref "D411") (pin "3") (pinfunction "ANODE_/_CATHODE_3") (pintype "passive"))
    )
    (net (code "29") (name "Net-(D435-ANODE_{slash}_CATHODE)") (class "Default")
      (node (ref "C435") (pin "2") (pinfunction "2_2") (pintype "passive"))
      (node (ref "D435") (pin "3") (pinfunction "ANODE_/_CATHODE_3") (pintype "passive"))
      (node (ref "R435") (pin "2") (pinfunction "2_2") (pintype "passive"))
    )
    (net (code "30") (name "Net-(D441-ANODE_{slash}_CATHODE)") (class "Default")
      (node (ref "C441") (pin "2") (pinfunction "2_2") (pintype "passive"))
      (node (ref "D441") (pin "3") (pinfunction "ANODE_/_CATHODE_3") (pintype "passive"))
    )
    (net (code "31") (name "Net-(JP421-Pad1)") (class "Default")
      (node (ref "JP421") (pin "1") (pinfunction "1_1") (pintype "passive"))
      (node (ref "L420") (pin "2") (pinfunction "2_2") (pintype "passive"))
      (node (ref "L421") (pin "1") (pinfunction "1_1") (pintype "passive"))
    )
    (net (code "32") (name "Net-(Q400-GATE)") (class "Default")
      (node (ref "Q400") (pin "4") (pinfunction "GATE_4") (pintype "passive"))
      (node (ref "R400") (pin "1") (pinfunction "1_1") (pintype "passive"))
    )
    (net (code "33") (name "Net-(Q401-GATE)") (class "Default")
      (node (ref "Q401") (pin "4") (pinfunction "GATE_4") (pintype "passive"))
      (node (ref "R401") (pin "1") (pinfunction "1_1") (pintype "passive"))
    )
    (net (code "34") (name "Net-(Q430-GATE)") (class "Default")
      (node (ref "Q430") (pin "4") (pinfunction "GATE_4") (pintype "passive"))
      (node (ref "R430") (pin "2") (pinfunction "2_2") (pintype "passive"))
    )
    (net (code "35") (name "Net-(Q431-GATE)") (class "Default")
      (node (ref "Q431") (pin "4") (pinfunction "GATE_4") (pintype "passive"))
      (node (ref "R431") (pin "2") (pinfunction "2_2") (pintype "passive"))
    )
    (net (code "36") (name "Net-(R402-Pad2)") (class "Default")
      (node (ref "R402") (pin "2") (pinfunction "2_2") (pintype "passive"))
      (node (ref "R403") (pin "1") (pinfunction "1_1") (pintype "passive"))
    )
    (net (code "37") (name "Net-(R420-V2)") (class "Default")
      (node (ref "L420") (pin "1") (pinfunction "1_1") (pintype "passive"))
      (node (ref "R420") (pin "2") (pinfunction "V2_2") (pintype "passive"))
    )
    (net (code "38") (name "Net-(U400-HO)") (class "Default")
      (node (ref "R400") (pin "2") (pinfunction "2_2") (pintype "passive"))
      (node (ref "U400") (pin "7") (pinfunction "HO_7") (pintype "output"))
    )
    (net (code "39") (name "Net-(U400-LO)") (class "Default")
      (node (ref "R401") (pin "2") (pinfunction "2_2") (pintype "passive"))
      (node (ref "U400") (pin "4") (pinfunction "LO_4") (pintype "output"))
    )
    (net (code "40") (name "Net-(U430-HO)") (class "Default")
      (node (ref "R430") (pin "1") (pinfunction "1_1") (pintype "passive"))
      (node (ref "U430") (pin "7") (pinfunction "HO_7") (pintype "output"))
    )
    (net (code "41") (name "Net-(U430-LO)") (class "Default")
      (node (ref "R431") (pin "1") (pinfunction "1_1") (pintype "passive"))
      (node (ref "U430") (pin "4") (pinfunction "LO_4") (pintype "output"))
    )
    (net (code "42") (name "unconnected-(D402-CATHODE-Pad2)") (class "Default")
      (node (ref "D402") (pin "2") (pinfunction "CATHODE_2") (pintype "passive+no_connect"))
    )
    (net (code "43") (name "unconnected-(D405-CATHODE-Pad2)") (class "Default")
      (node (ref "D405") (pin "2") (pinfunction "CATHODE_2") (pintype "passive+no_connect"))
    )
    (net (code "44") (name "unconnected-(D410-NC-Pad2)") (class "Default")
      (node (ref "D410") (pin "2") (pinfunction "NC_2") (pintype "passive+no_connect"))
    )
    (net (code "45") (name "unconnected-(D432-CATHODE-Pad2)") (class "Default")
      (node (ref "D432") (pin "2") (pinfunction "CATHODE_2") (pintype "passive+no_connect"))
    )
    (net (code "46") (name "unconnected-(D433-NC-Pad2)") (class "Default")
      (node (ref "D433") (pin "2") (pinfunction "NC_2") (pintype "passive+no_connect"))
    )
    (net (code "47") (name "unconnected-(D435-CATHODE-Pad2)") (class "Default")
      (node (ref "D435") (pin "2") (pinfunction "CATHODE_2") (pintype "passive+no_connect"))
    )
    (net (code "48") (name "unconnected-(D440-NC-Pad2)") (class "Default")
      (node (ref "D440") (pin "2") (pinfunction "NC_2") (pintype "passive+no_connect"))
    )
    (net (code "49") (name "unconnected-(D442-CATHODE-Pad2)") (class "Default")
      (node (ref "D442") (pin "2") (pinfunction "CATHODE_2") (pintype "passive+no_connect"))
    )
    (net (code "50") (name "unconnected-(D443-CATHODE-Pad2)") (class "Default")
      (node (ref "D443") (pin "2") (pinfunction "CATHODE_2") (pintype "passive+no_connect"))
    )
    (net (code "51") (name "unconnected-(U410-CV-Pad5)") (class "Default")
      (node (ref "U410") (pin "5") (pinfunction "CV_5") (pintype "power_in+no_connect"))
    )
    (net (code "52") (name "unconnected-(U410-DC-Pad7)") (class "Default")
      (node (ref "U410") (pin "7") (pinfunction "DC_7") (pintype "passive+no_connect"))
    )
    (net (code "53") (name "unconnected-(U440-CV-Pad5)") (class "Default")
      (node (ref "U440") (pin "5") (pinfunction "CV_5") (pintype "power_in+no_connect"))
    )
    (net (code "54") (name "unconnected-(U440-DC-Pad7)") (class "Default")
      (node (ref "U440") (pin "7") (pinfunction "DC_7") (pintype "passive+no_connect"))
    )
  )
)
